# FM-Super-Regenerative-KosmosX3000.net
KiCad netlist of a schematic drawn in EAGLE
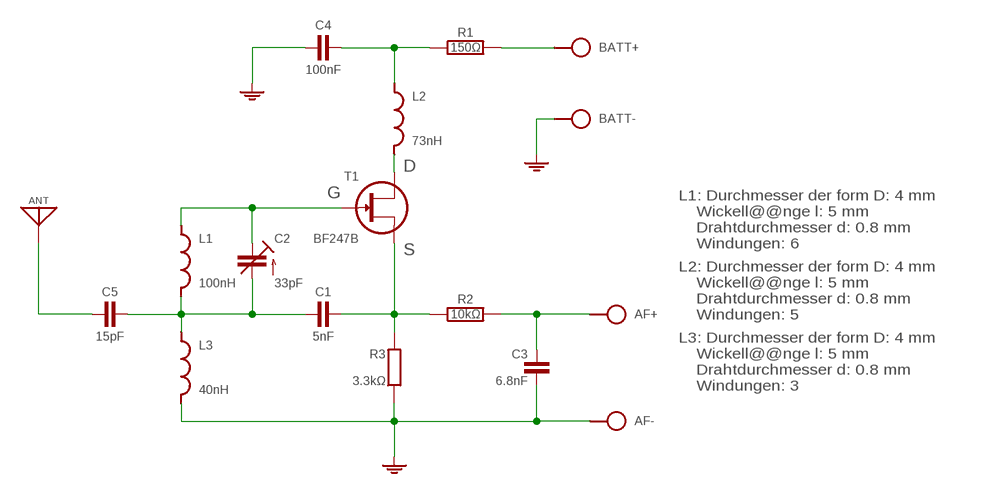
[diagram p0: schematic, sheet 1]

(export (version "E")
  (design (tool "Eeschema 10.0.6"))
  (components
    (comp (ref "AF")
      (value "SPAD+-+-")
      (footprint "eagle-import:SPAD+-")
      (libsource (lib "eagle-import") (part "SPAD+-+-"))
    )
    (comp (ref "ANT")
      (value "ANT")
      (footprint "eagle-import:SPAD")
      (libsource (lib "eagle-import") (part "ANT"))
    )
    (comp (ref "BATT")
      (value "SPAD+--+")
      (footprint "eagle-import:SPAD-+")
      (libsource (lib "eagle-import") (part "SPAD+--+"))
    )
    (comp (ref "C1")
      (value "5nF")
      (footprint "eagle-import:C050-020X044")
      (libsource (lib "eagle-import") (part "C050-020X044"))
    )
    (comp (ref "C2")
      (value "33pF")
      (footprint "eagle-import:TRIM-2222-808")
      (libsource (lib "eagle-import") (part "C-TR-PH201272222-808-2PIN"))
    )
    (comp (ref "C3")
      (value "6.8nF")
      (footprint "eagle-import:C050-020X044")
      (libsource (lib "eagle-import") (part "C050-020X044"))
    )
    (comp (ref "C4")
      (value "100nF")
      (footprint "eagle-import:C050-020X044")
      (libsource (lib "eagle-import") (part "C050-020X044"))
    )
    (comp (ref "C5")
      (value "15pF")
      (footprint "eagle-import:C025-015X024")
      (libsource (lib "eagle-import") (part "C025-015X024"))
    )
    (comp (ref "L1")
      (value "100nH")
      (footprint "eagle-import:L-04-5_6V-C")
      (libsource (lib "eagle-import") (part "L-SHORT04-5/5V-C"))
    )
    (comp (ref "L2")
      (value "73nH")
      (footprint "eagle-import:L-04-5_6V-C")
      (libsource (lib "eagle-import") (part "L-SHORT04-5/5V-C"))
    )
    (comp (ref "L3")
      (value "40nH")
      (footprint "eagle-import:L-04-5_6V-C")
      (libsource (lib "eagle-import") (part "L-SHORT04-5/5V-C"))
    )
    (comp (ref "R1")
      (value "150Ω")
      (footprint "eagle-import:0204_15-V")
      (libsource (lib "eagle-import") (part "R-H0204/15-V"))
    )
    (comp (ref "R2")
      (value "10kΩ")
      (footprint "eagle-import:0204_10-V")
      (libsource (lib "eagle-import") (part "R-H0204/10-V"))
    )
    (comp (ref "R3")
      (value "3.3kΩ")
      (footprint "eagle-import:0204_10-V")
      (libsource (lib "eagle-import") (part "R0204/10-V"))
    )
    (comp (ref "T1")
      (value "BF247B")
      (footprint "eagle-import:TO92")
      (libsource (lib "eagle-import") (part "BF247B"))
    )
  )
  (nets
    (net (code "1") (name "GND") (class "Default")
      (node (ref "AF") (pin "1") (pinfunction "P$1_1") (pintype "passive"))
      (node (ref "BATT") (pin "1") (pinfunction "P$1_1") (pintype "passive"))
      (node (ref "C3") (pin "2") (pinfunction "2_2") (pintype "passive"))
      (node (ref "C4") (pin "2") (pinfunction "2_2") (pintype "passive"))
      (node (ref "L3") (pin "1") (pinfunction "1_1") (pintype "passive"))
      (node (ref "R3") (pin "2") (pinfunction "1_2") (pintype "passive"))
    )
    (net (code "2") (name "Net-(AFA-P$1)") (class "Default")
      (node (ref "AF") (pin "2") (pinfunction "P$1_2") (pintype "passive"))
      (node (ref "C3") (pin "1") (pinfunction "1_1") (pintype "passive"))
      (node (ref "R2") (pin "2") (pinfunction "2_2") (pintype "passive"))
    )
    (net (code "3") (name "Net-(ANT-Pad1)") (class "Default")
      (node (ref "ANT") (pin "1") (pinfunction "1_1") (pintype "output"))
      (node (ref "C5") (pin "2") (pinfunction "2_2") (pintype "passive"))
    )
    (net (code "4") (name "Net-(BATTA-P$1)") (class "Default")
      (node (ref "BATT") (pin "2") (pinfunction "P$1_2") (pintype "passive"))
      (node (ref "R1") (pin "2") (pinfunction "2_2") (pintype "passive"))
    )
    (net (code "5") (name "Net-(C2-A)") (class "Default")
      (node (ref "C1") (pin "2") (pinfunction "2_2") (pintype "passive"))
      (node (ref "C2") (pin "2") (pinfunction "A_2") (pintype "passive"))
      (node (ref "C5") (pin "1") (pinfunction "1_1") (pintype "passive"))
      (node (ref "L1") (pin "1") (pinfunction "1_1") (pintype "passive"))
      (node (ref "L3") (pin "2") (pinfunction "2_2") (pintype "passive"))
    )
    (net (code "6") (name "Net-(C2-E)") (class "Default")
      (node (ref "C2") (pin "1") (pinfunction "E_1") (pintype "passive"))
      (node (ref "L1") (pin "2") (pinfunction "2_2") (pintype "passive"))
      (node (ref "T1") (pin "3") (pinfunction "G_3") (pintype "passive"))
    )
    (net (code "7") (name "Net-(C4-Pad1)") (class "Default")
      (node (ref "C4") (pin "1") (pinfunction "1_1") (pintype "passive"))
      (node (ref "L2") (pin "2") (pinfunction "2_2") (pintype "passive"))
      (node (ref "R1") (pin "1") (pinfunction "1_1") (pintype "passive"))
    )
    (net (code "8") (name "Net-(R3-2)") (class "Default")
      (node (ref "C1") (pin "1") (pinfunction "1_1") (pintype "passive"))
      (node (ref "R2") (pin "1") (pinfunction "1_1") (pintype "passive"))
      (node (ref "R3") (pin "1") (pinfunction "2_1") (pintype "passive"))
      (node (ref "T1") (pin "2") (pinfunction "S_2") (pintype "passive"))
    )
    (net (code "9") (name "Net-(T1-D)") (class "Default")
      (node (ref "L2") (pin "1") (pinfunction "1_1") (pintype "passive"))
      (node (ref "T1") (pin "1") (pinfunction "D_1") (pintype "passive"))
    )
  )
)
